# RollerBallRacerController.net
KiCad netlist of a schematic drawn in EAGLE
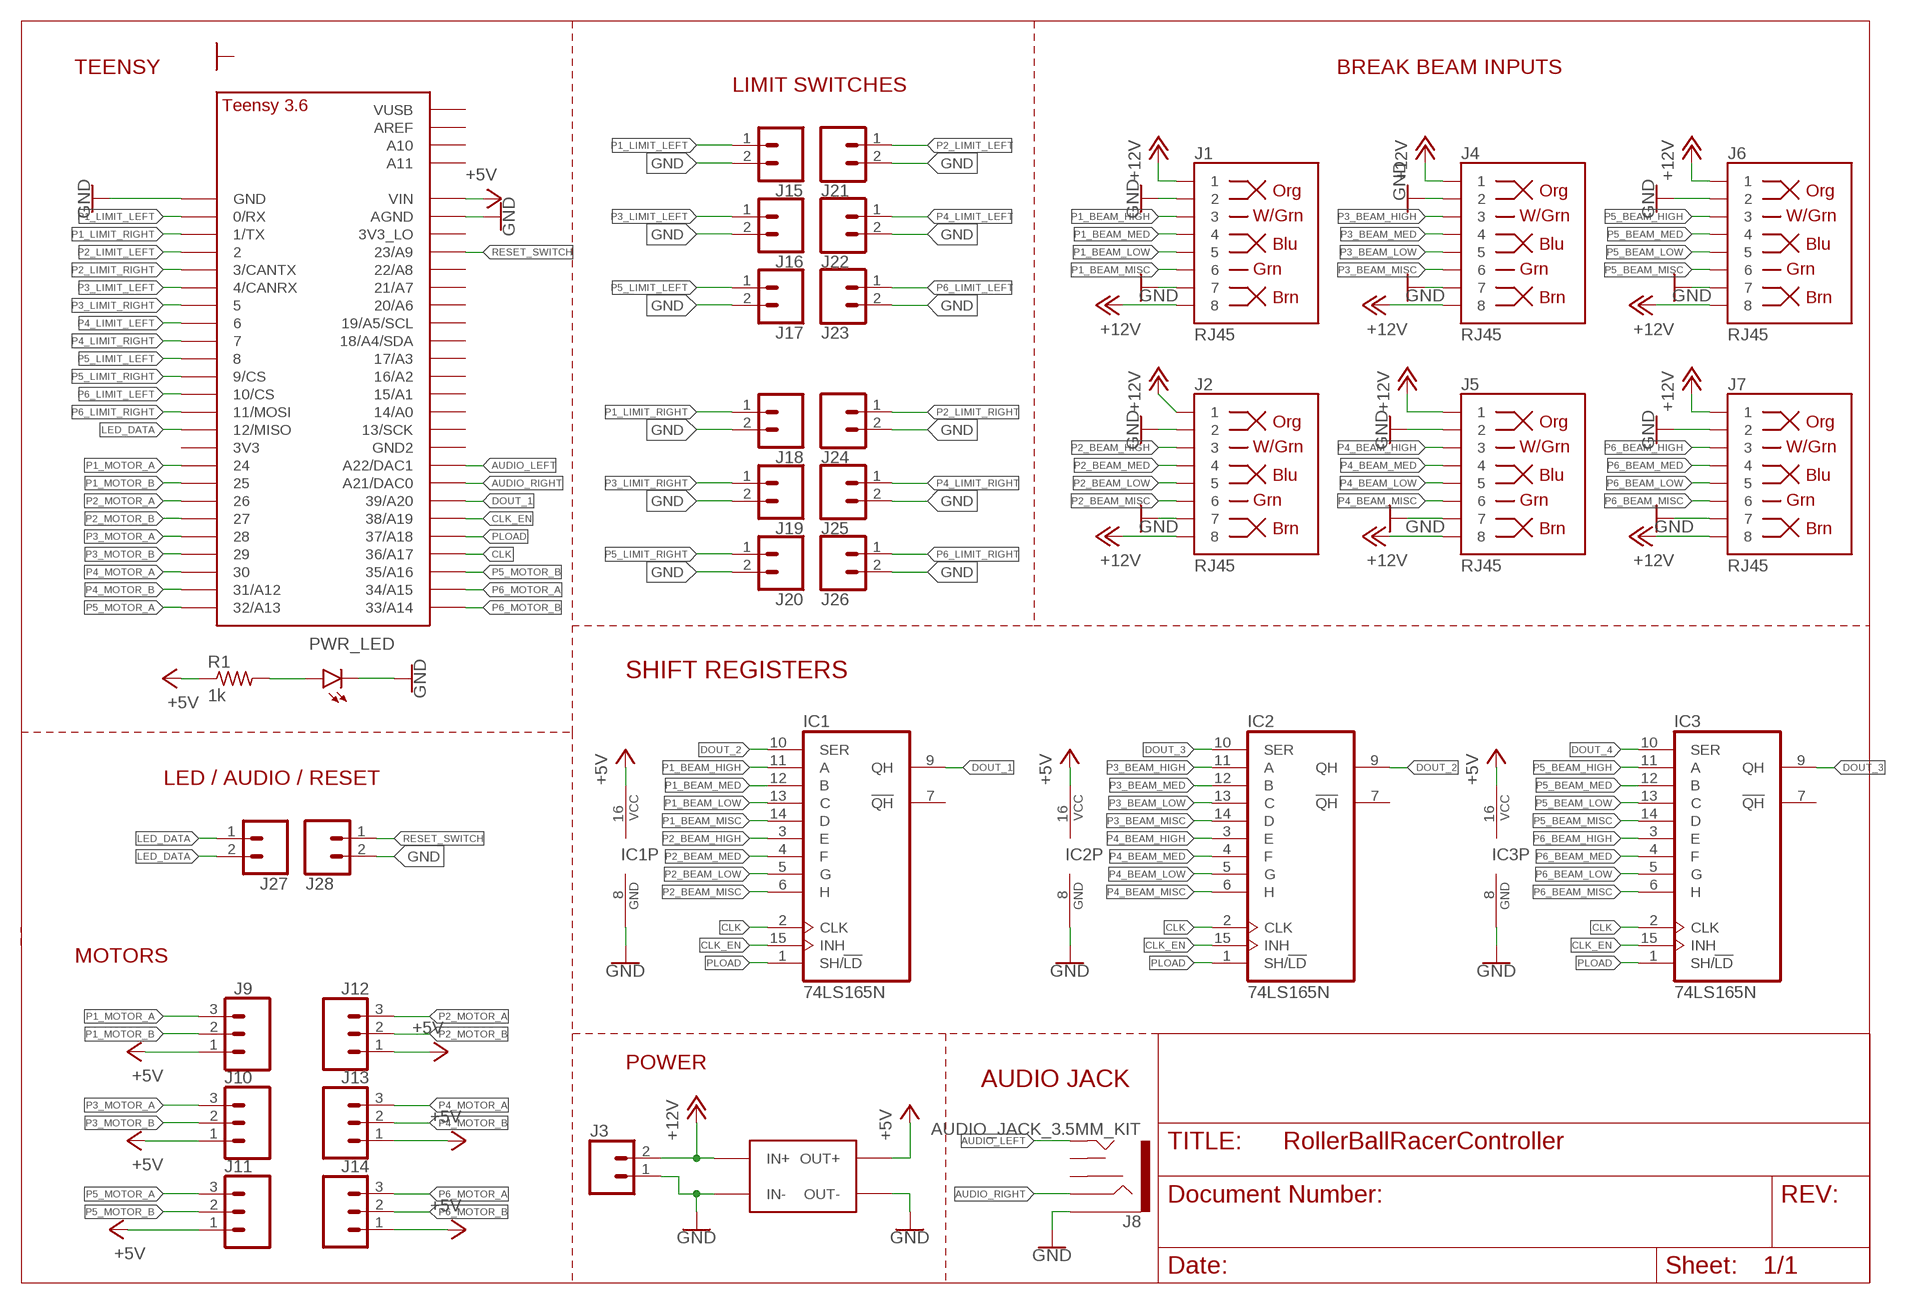
[diagram p0: schematic, sheet 1]

(export (version "E")
  (design (tool "Eeschema 10.0.6"))
  (components
    (comp (ref "IC1")
      (value "74LS165N")
      (footprint "eagle-import:DIL16")
      (libsource (lib "eagle-import") (part "74165NLS"))
    )
    (comp (ref "IC2")
      (value "74LS165N")
      (footprint "eagle-import:DIL16")
      (libsource (lib "eagle-import") (part "74165NLS"))
    )
    (comp (ref "IC3")
      (value "74LS165N")
      (footprint "eagle-import:DIL16")
      (libsource (lib "eagle-import") (part "74165NLS"))
    )
    (comp (ref "J1")
      (value "RJ45")
      (footprint "eagle-import:RJ45-8")
      (libsource (lib "eagle-import") (part "RJ45-8"))
    )
    (comp (ref "J2")
      (value "RJ45")
      (footprint "eagle-import:RJ45-8")
      (libsource (lib "eagle-import") (part "RJ45-8"))
    )
    (comp (ref "J3")
      (value "CONN_025MM")
      (footprint "eagle-import:SCREWTERMINAL-5MM-2")
      (libsource (lib "eagle-import") (part "CONN_025MM"))
    )
    (comp (ref "J4")
      (value "RJ45")
      (footprint "eagle-import:RJ45-8")
      (libsource (lib "eagle-import") (part "RJ45-8"))
    )
    (comp (ref "J5")
      (value "RJ45")
      (footprint "eagle-import:RJ45-8")
      (libsource (lib "eagle-import") (part "RJ45-8"))
    )
    (comp (ref "J6")
      (value "RJ45")
      (footprint "eagle-import:RJ45-8")
      (libsource (lib "eagle-import") (part "RJ45-8"))
    )
    (comp (ref "J7")
      (value "RJ45")
      (footprint "eagle-import:RJ45-8")
      (libsource (lib "eagle-import") (part "RJ45-8"))
    )
    (comp (ref "J8")
      (value "AUDIO_JACK_3.5MM_KIT")
      (footprint "eagle-import:AUDIO-JACK-KIT")
      (libsource (lib "eagle-import") (part "AUDIO_JACK_3.5MM_KIT"))
    )
    (comp (ref "J9")
      (value "CONN_03POLAR")
      (footprint "eagle-import:MOLEX-1X3")
      (libsource (lib "eagle-import") (part "CONN_03POLAR"))
    )
    (comp (ref "J10")
      (value "CONN_03POLAR")
      (footprint "eagle-import:MOLEX-1X3")
      (libsource (lib "eagle-import") (part "CONN_03POLAR"))
    )
    (comp (ref "J11")
      (value "CONN_03POLAR")
      (footprint "eagle-import:MOLEX-1X3")
      (libsource (lib "eagle-import") (part "CONN_03POLAR"))
    )
    (comp (ref "J12")
      (value "CONN_03POLAR")
      (footprint "eagle-import:MOLEX-1X3")
      (libsource (lib "eagle-import") (part "CONN_03POLAR"))
    )
    (comp (ref "J13")
      (value "CONN_03POLAR")
      (footprint "eagle-import:MOLEX-1X3")
      (libsource (lib "eagle-import") (part "CONN_03POLAR"))
    )
    (comp (ref "J14")
      (value "CONN_03POLAR")
      (footprint "eagle-import:MOLEX-1X3")
      (libsource (lib "eagle-import") (part "CONN_03POLAR"))
    )
    (comp (ref "J15")
      (value "CONN_02POLAR")
      (footprint "eagle-import:MOLEX-1X2")
      (libsource (lib "eagle-import") (part "CONN_02POLAR"))
    )
    (comp (ref "J16")
      (value "CONN_02POLAR")
      (footprint "eagle-import:MOLEX-1X2")
      (libsource (lib "eagle-import") (part "CONN_02POLAR"))
    )
    (comp (ref "J17")
      (value "CONN_02POLAR")
      (footprint "eagle-import:MOLEX-1X2")
      (libsource (lib "eagle-import") (part "CONN_02POLAR"))
    )
    (comp (ref "J18")
      (value "CONN_02POLAR")
      (footprint "eagle-import:MOLEX-1X2")
      (libsource (lib "eagle-import") (part "CONN_02POLAR"))
    )
    (comp (ref "J19")
      (value "CONN_02POLAR")
      (footprint "eagle-import:MOLEX-1X2")
      (libsource (lib "eagle-import") (part "CONN_02POLAR"))
    )
    (comp (ref "J20")
      (value "CONN_02POLAR")
      (footprint "eagle-import:MOLEX-1X2")
      (libsource (lib "eagle-import") (part "CONN_02POLAR"))
    )
    (comp (ref "J21")
      (value "CONN_02POLAR")
      (footprint "eagle-import:MOLEX-1X2")
      (libsource (lib "eagle-import") (part "CONN_02POLAR"))
    )
    (comp (ref "J22")
      (value "CONN_02POLAR")
      (footprint "eagle-import:MOLEX-1X2")
      (libsource (lib "eagle-import") (part "CONN_02POLAR"))
    )
    (comp (ref "J23")
      (value "CONN_02POLAR")
      (footprint "eagle-import:MOLEX-1X2")
      (libsource (lib "eagle-import") (part "CONN_02POLAR"))
    )
    (comp (ref "J24")
      (value "CONN_02POLAR")
      (footprint "eagle-import:MOLEX-1X2")
      (libsource (lib "eagle-import") (part "CONN_02POLAR"))
    )
    (comp (ref "J25")
      (value "CONN_02POLAR")
      (footprint "eagle-import:MOLEX-1X2")
      (libsource (lib "eagle-import") (part "CONN_02POLAR"))
    )
    (comp (ref "J26")
      (value "CONN_02POLAR")
      (footprint "eagle-import:MOLEX-1X2")
      (libsource (lib "eagle-import") (part "CONN_02POLAR"))
    )
    (comp (ref "J27")
      (value "CONN_02POLAR")
      (footprint "eagle-import:MOLEX-1X2")
      (libsource (lib "eagle-import") (part "CONN_02POLAR"))
    )
    (comp (ref "J28")
      (value "CONN_02POLAR")
      (footprint "eagle-import:MOLEX-1X2")
      (libsource (lib "eagle-import") (part "CONN_02POLAR"))
    )
    (comp (ref "PWR_LED")
      (value "LED5MM")
      (footprint "eagle-import:LED5MM")
      (libsource (lib "eagle-import") (part "LED5MM"))
    )
    (comp (ref "R1")
      (value "1k")
      (footprint "eagle-import:0204_7")
      (libsource (lib "eagle-import") (part "R-US_0204/7"))
    )
    (comp (ref "U$2")
      (value "LM2956_DC_DC")
      (footprint "eagle-import:LM2596")
      (libsource (lib "eagle-import") (part "LM2956_DC_DC"))
    )
    (comp (ref "U$3")
      (value "TEENSY_3.5/3.6_BASIC")
      (footprint "eagle-import:TEENSY_3.5_3.6_BASIC")
      (libsource (lib "eagle-import") (part "TEENSY_3.5/3.6_BASIC"))
    )
  )
  (nets
    (net (code "1") (name "+5V") (class "Default")
      (node (ref "IC1") (pin "16") (pinfunction "VCC_16") (pintype "power_in"))
      (node (ref "IC2") (pin "16") (pinfunction "VCC_16") (pintype "power_in"))
      (node (ref "IC3") (pin "16") (pinfunction "VCC_16") (pintype "power_in"))
      (node (ref "J10") (pin "1") (pinfunction "1_1") (pintype "passive"))
      (node (ref "J11") (pin "1") (pinfunction "1_1") (pintype "passive"))
      (node (ref "J12") (pin "1") (pinfunction "1_1") (pintype "passive"))
      (node (ref "J13") (pin "1") (pinfunction "1_1") (pintype "passive"))
      (node (ref "J14") (pin "1") (pinfunction "1_1") (pintype "passive"))
      (node (ref "J9") (pin "1") (pinfunction "1_1") (pintype "passive"))
      (node (ref "R1") (pin "1") (pinfunction "1_1") (pintype "passive"))
      (node (ref "U$2") (pin "P$4") (pinfunction "OUT+_P$4") (pintype "bidirectional"))
      (node (ref "U$3") (pin "VIN") (pinfunction "VIN_VIN") (pintype "bidirectional"))
    )
    (net (code "2") (name "+12V") (class "Default")
      (node (ref "J1") (pin "1") (pinfunction "1_1") (pintype "bidirectional"))
      (node (ref "J1") (pin "8") (pinfunction "8_8") (pintype "bidirectional"))
      (node (ref "J2") (pin "1") (pinfunction "1_1") (pintype "bidirectional"))
      (node (ref "J2") (pin "8") (pinfunction "8_8") (pintype "bidirectional"))
      (node (ref "J3") (pin "2") (pinfunction "2_2") (pintype "passive"))
      (node (ref "J4") (pin "1") (pinfunction "1_1") (pintype "bidirectional"))
      (node (ref "J4") (pin "8") (pinfunction "8_8") (pintype "bidirectional"))
      (node (ref "J5") (pin "1") (pinfunction "1_1") (pintype "bidirectional"))
      (node (ref "J5") (pin "8") (pinfunction "8_8") (pintype "bidirectional"))
      (node (ref "J6") (pin "1") (pinfunction "1_1") (pintype "bidirectional"))
      (node (ref "J6") (pin "8") (pinfunction "8_8") (pintype "bidirectional"))
      (node (ref "J7") (pin "1") (pinfunction "1_1") (pintype "bidirectional"))
      (node (ref "J7") (pin "8") (pinfunction "8_8") (pintype "bidirectional"))
      (node (ref "U$2") (pin "P$1") (pinfunction "IN+_P$1") (pintype "bidirectional"))
    )
    (net (code "3") (name "AUDIO_LEFT") (class "Default")
      (node (ref "J8") (pin "TIP") (pinfunction "TIP_TIP") (pintype "bidirectional"))
      (node (ref "U$3") (pin "A22/DAC1") (pinfunction "A22/DAC1_A22/DAC1") (pintype "bidirectional"))
    )
    (net (code "4") (name "AUDIO_RIGHT") (class "Default")
      (node (ref "J8") (pin "RING") (pinfunction "RING_RING") (pintype "bidirectional"))
      (node (ref "U$3") (pin "21/DAC0") (pinfunction "A21/DAC0_21/DAC0") (pintype "bidirectional"))
    )
    (net (code "5") (name "CLK") (class "Default")
      (node (ref "IC1") (pin "2") (pinfunction "CLK_2") (pintype "input"))
      (node (ref "IC2") (pin "2") (pinfunction "CLK_2") (pintype "input"))
      (node (ref "IC3") (pin "2") (pinfunction "CLK_2") (pintype "input"))
      (node (ref "U$3") (pin "36/A17") (pinfunction "36/A17_36/A17") (pintype "bidirectional"))
    )
    (net (code "6") (name "CLK_EN") (class "Default")
      (node (ref "IC1") (pin "15") (pinfunction "INH_15") (pintype "input"))
      (node (ref "IC2") (pin "15") (pinfunction "INH_15") (pintype "input"))
      (node (ref "IC3") (pin "15") (pinfunction "INH_15") (pintype "input"))
      (node (ref "U$3") (pin "38/A19") (pinfunction "38/A19_38/A19") (pintype "bidirectional"))
    )
    (net (code "7") (name "DOUT_1") (class "Default")
      (node (ref "IC1") (pin "9") (pinfunction "QH_9") (pintype "output"))
      (node (ref "U$3") (pin "39/A20") (pinfunction "39/A20_39/A20") (pintype "bidirectional"))
    )
    (net (code "8") (name "DOUT_2") (class "Default")
      (node (ref "IC1") (pin "10") (pinfunction "SER_10") (pintype "input"))
      (node (ref "IC2") (pin "9") (pinfunction "QH_9") (pintype "output"))
    )
    (net (code "9") (name "DOUT_3") (class "Default")
      (node (ref "IC2") (pin "10") (pinfunction "SER_10") (pintype "input"))
      (node (ref "IC3") (pin "9") (pinfunction "QH_9") (pintype "output"))
    )
    (net (code "10") (name "DOUT_4") (class "Default")
      (node (ref "IC3") (pin "10") (pinfunction "SER_10") (pintype "input"))
    )
    (net (code "11") (name "GND") (class "Default")
      (node (ref "IC1") (pin "8") (pinfunction "GND_8") (pintype "power_in"))
      (node (ref "IC2") (pin "8") (pinfunction "GND_8") (pintype "power_in"))
      (node (ref "IC3") (pin "8") (pinfunction "GND_8") (pintype "power_in"))
      (node (ref "J1") (pin "2") (pinfunction "2_2") (pintype "bidirectional"))
      (node (ref "J1") (pin "7") (pinfunction "7_7") (pintype "bidirectional"))
      (node (ref "J15") (pin "2") (pinfunction "2_2") (pintype "passive"))
      (node (ref "J16") (pin "2") (pinfunction "2_2") (pintype "passive"))
      (node (ref "J17") (pin "2") (pinfunction "2_2") (pintype "passive"))
      (node (ref "J18") (pin "2") (pinfunction "2_2") (pintype "passive"))
      (node (ref "J19") (pin "2") (pinfunction "2_2") (pintype "passive"))
      (node (ref "J2") (pin "2") (pinfunction "2_2") (pintype "bidirectional"))
      (node (ref "J2") (pin "7") (pinfunction "7_7") (pintype "bidirectional"))
      (node (ref "J20") (pin "2") (pinfunction "2_2") (pintype "passive"))
      (node (ref "J21") (pin "2") (pinfunction "2_2") (pintype "passive"))
      (node (ref "J22") (pin "2") (pinfunction "2_2") (pintype "passive"))
      (node (ref "J23") (pin "2") (pinfunction "2_2") (pintype "passive"))
      (node (ref "J24") (pin "2") (pinfunction "2_2") (pintype "passive"))
      (node (ref "J25") (pin "2") (pinfunction "2_2") (pintype "passive"))
      (node (ref "J26") (pin "2") (pinfunction "2_2") (pintype "passive"))
      (node (ref "J28") (pin "2") (pinfunction "2_2") (pintype "passive"))
      (node (ref "J3") (pin "1") (pinfunction "1_1") (pintype "passive"))
      (node (ref "J4") (pin "2") (pinfunction "2_2") (pintype "bidirectional"))
      (node (ref "J4") (pin "7") (pinfunction "7_7") (pintype "bidirectional"))
      (node (ref "J5") (pin "2") (pinfunction "2_2") (pintype "bidirectional"))
      (node (ref "J5") (pin "7") (pinfunction "7_7") (pintype "bidirectional"))
      (node (ref "J6") (pin "2") (pinfunction "2_2") (pintype "bidirectional"))
      (node (ref "J6") (pin "7") (pinfunction "7_7") (pintype "bidirectional"))
      (node (ref "J7") (pin "2") (pinfunction "2_2") (pintype "bidirectional"))
      (node (ref "J7") (pin "7") (pinfunction "7_7") (pintype "bidirectional"))
      (node (ref "J8") (pin "SLEEVE") (pinfunction "SLEEVE_SLEEVE") (pintype "bidirectional"))
      (node (ref "PWR_LED") (pin "K") (pinfunction "C_K") (pintype "passive"))
      (node (ref "U$2") (pin "P$2") (pinfunction "IN-_P$2") (pintype "bidirectional"))
      (node (ref "U$2") (pin "P$3") (pinfunction "OUT-_P$3") (pintype "bidirectional"))
      (node (ref "U$3") (pin "AGND") (pinfunction "AGND_AGND") (pintype "bidirectional"))
      (node (ref "U$3") (pin "GND") (pinfunction "GND_GND") (pintype "bidirectional"))
    )
    (net (code "12") (name "LED_DATA") (class "Default")
      (node (ref "J27") (pin "1") (pinfunction "1_1") (pintype "passive"))
      (node (ref "J27") (pin "2") (pinfunction "2_2") (pintype "passive"))
      (node (ref "U$3") (pin "12/MISO") (pinfunction "12/MISO_12/MISO") (pintype "bidirectional"))
    )
    (net (code "13") (name "Net-(PWR_LED-PadA)") (class "Default")
      (node (ref "PWR_LED") (pin "A") (pinfunction "A_A") (pintype "passive"))
      (node (ref "R1") (pin "2") (pinfunction "2_2") (pintype "passive"))
    )
    (net (code "14") (name "P1_BEAM_HIGH") (class "Default")
      (node (ref "IC1") (pin "11") (pinfunction "A_11") (pintype "input"))
      (node (ref "J1") (pin "3") (pinfunction "3_3") (pintype "bidirectional"))
    )
    (net (code "15") (name "P1_BEAM_LOW") (class "Default")
      (node (ref "IC1") (pin "13") (pinfunction "C_13") (pintype "input"))
      (node (ref "J1") (pin "5") (pinfunction "5_5") (pintype "bidirectional"))
    )
    (net (code "16") (name "P1_BEAM_MED") (class "Default")
      (node (ref "IC1") (pin "12") (pinfunction "B_12") (pintype "input"))
      (node (ref "J1") (pin "4") (pinfunction "4_4") (pintype "bidirectional"))
    )
    (net (code "17") (name "P1_BEAM_MISC") (class "Default")
      (node (ref "IC1") (pin "14") (pinfunction "D_14") (pintype "input"))
      (node (ref "J1") (pin "6") (pinfunction "6_6") (pintype "bidirectional"))
    )
    (net (code "18") (name "P1_LIMIT_LEFT") (class "Default")
      (node (ref "J15") (pin "1") (pinfunction "1_1") (pintype "passive"))
      (node (ref "U$3") (pin "0/RX") (pinfunction "0/RX_0/RX") (pintype "bidirectional"))
    )
    (net (code "19") (name "P1_LIMIT_RIGHT") (class "Default")
      (node (ref "J18") (pin "1") (pinfunction "1_1") (pintype "passive"))
      (node (ref "U$3") (pin "1/TX") (pinfunction "1/TX_1/TX") (pintype "bidirectional"))
    )
    (net (code "20") (name "P1_MOTOR_A") (class "Default")
      (node (ref "J9") (pin "3") (pinfunction "3_3") (pintype "passive"))
      (node (ref "U$3") (pin "24") (pinfunction "24_24") (pintype "bidirectional"))
    )
    (net (code "21") (name "P1_MOTOR_B") (class "Default")
      (node (ref "J9") (pin "2") (pinfunction "2_2") (pintype "passive"))
      (node (ref "U$3") (pin "25") (pinfunction "25_25") (pintype "bidirectional"))
    )
    (net (code "22") (name "P2_BEAM_HIGH") (class "Default")
      (node (ref "IC1") (pin "3") (pinfunction "E_3") (pintype "input"))
      (node (ref "J2") (pin "3") (pinfunction "3_3") (pintype "bidirectional"))
    )
    (net (code "23") (name "P2_BEAM_LOW") (class "Default")
      (node (ref "IC1") (pin "5") (pinfunction "G_5") (pintype "input"))
      (node (ref "J2") (pin "5") (pinfunction "5_5") (pintype "bidirectional"))
    )
    (net (code "24") (name "P2_BEAM_MED") (class "Default")
      (node (ref "IC1") (pin "4") (pinfunction "F_4") (pintype "input"))
      (node (ref "J2") (pin "4") (pinfunction "4_4") (pintype "bidirectional"))
    )
    (net (code "25") (name "P2_BEAM_MISC") (class "Default")
      (node (ref "IC1") (pin "6") (pinfunction "H_6") (pintype "input"))
      (node (ref "J2") (pin "6") (pinfunction "6_6") (pintype "bidirectional"))
    )
    (net (code "26") (name "P2_LIMIT_LEFT") (class "Default")
      (node (ref "J21") (pin "1") (pinfunction "1_1") (pintype "passive"))
      (node (ref "U$3") (pin "2") (pinfunction "2_2") (pintype "bidirectional"))
    )
    (net (code "27") (name "P2_LIMIT_RIGHT") (class "Default")
      (node (ref "J24") (pin "1") (pinfunction "1_1") (pintype "passive"))
      (node (ref "U$3") (pin "3/CANTX") (pinfunction "3/CANTX_3/CANTX") (pintype "bidirectional"))
    )
    (net (code "28") (name "P2_MOTOR_A") (class "Default")
      (node (ref "J12") (pin "3") (pinfunction "3_3") (pintype "passive"))
      (node (ref "U$3") (pin "26") (pinfunction "26_26") (pintype "bidirectional"))
    )
    (net (code "29") (name "P2_MOTOR_B") (class "Default")
      (node (ref "J12") (pin "2") (pinfunction "2_2") (pintype "passive"))
      (node (ref "U$3") (pin "27") (pinfunction "27_27") (pintype "bidirectional"))
    )
    (net (code "30") (name "P3_BEAM_HIGH") (class "Default")
      (node (ref "IC2") (pin "11") (pinfunction "A_11") (pintype "input"))
      (node (ref "J4") (pin "3") (pinfunction "3_3") (pintype "bidirectional"))
    )
    (net (code "31") (name "P3_BEAM_LOW") (class "Default")
      (node (ref "IC2") (pin "13") (pinfunction "C_13") (pintype "input"))
      (node (ref "J4") (pin "5") (pinfunction "5_5") (pintype "bidirectional"))
    )
    (net (code "32") (name "P3_BEAM_MED") (class "Default")
      (node (ref "IC2") (pin "12") (pinfunction "B_12") (pintype "input"))
      (node (ref "J4") (pin "4") (pinfunction "4_4") (pintype "bidirectional"))
    )
    (net (code "33") (name "P3_BEAM_MISC") (class "Default")
      (node (ref "IC2") (pin "14") (pinfunction "D_14") (pintype "input"))
      (node (ref "J4") (pin "6") (pinfunction "6_6") (pintype "bidirectional"))
    )
    (net (code "34") (name "P3_LIMIT_LEFT") (class "Default")
      (node (ref "J16") (pin "1") (pinfunction "1_1") (pintype "passive"))
      (node (ref "U$3") (pin "4/CANRX") (pinfunction "4/CANRX_4/CANRX") (pintype "bidirectional"))
    )
    (net (code "35") (name "P3_LIMIT_RIGHT") (class "Default")
      (node (ref "J19") (pin "1") (pinfunction "1_1") (pintype "passive"))
      (node (ref "U$3") (pin "5") (pinfunction "5_5") (pintype "bidirectional"))
    )
    (net (code "36") (name "P3_MOTOR_A") (class "Default")
      (node (ref "J10") (pin "3") (pinfunction "3_3") (pintype "passive"))
      (node (ref "U$3") (pin "28") (pinfunction "28_28") (pintype "bidirectional"))
    )
    (net (code "37") (name "P3_MOTOR_B") (class "Default")
      (node (ref "J10") (pin "2") (pinfunction "2_2") (pintype "passive"))
      (node (ref "U$3") (pin "29") (pinfunction "29_29") (pintype "bidirectional"))
    )
    (net (code "38") (name "P4_BEAM_HIGH") (class "Default")
      (node (ref "IC2") (pin "3") (pinfunction "E_3") (pintype "input"))
      (node (ref "J5") (pin "3") (pinfunction "3_3") (pintype "bidirectional"))
    )
    (net (code "39") (name "P4_BEAM_LOW") (class "Default")
      (node (ref "IC2") (pin "5") (pinfunction "G_5") (pintype "input"))
      (node (ref "J5") (pin "5") (pinfunction "5_5") (pintype "bidirectional"))
    )
    (net (code "40") (name "P4_BEAM_MED") (class "Default")
      (node (ref "IC2") (pin "4") (pinfunction "F_4") (pintype "input"))
      (node (ref "J5") (pin "4") (pinfunction "4_4") (pintype "bidirectional"))
    )
    (net (code "41") (name "P4_BEAM_MISC") (class "Default")
      (node (ref "IC2") (pin "6") (pinfunction "H_6") (pintype "input"))
      (node (ref "J5") (pin "6") (pinfunction "6_6") (pintype "bidirectional"))
    )
    (net (code "42") (name "P4_LIMIT_LEFT") (class "Default")
      (node (ref "J22") (pin "1") (pinfunction "1_1") (pintype "passive"))
      (node (ref "U$3") (pin "6") (pinfunction "6_6") (pintype "bidirectional"))
    )
    (net (code "43") (name "P4_LIMIT_RIGHT") (class "Default")
      (node (ref "J25") (pin "1") (pinfunction "1_1") (pintype "passive"))
      (node (ref "U$3") (pin "7") (pinfunction "7_7") (pintype "bidirectional"))
    )
    (net (code "44") (name "P4_MOTOR_A") (class "Default")
      (node (ref "J13") (pin "3") (pinfunction "3_3") (pintype "passive"))
      (node (ref "U$3") (pin "30") (pinfunction "30_30") (pintype "bidirectional"))
    )
    (net (code "45") (name "P4_MOTOR_B") (class "Default")
      (node (ref "J13") (pin "2") (pinfunction "2_2") (pintype "passive"))
      (node (ref "U$3") (pin "31/A12") (pinfunction "31/A12_31/A12") (pintype "bidirectional"))
    )
    (net (code "46") (name "P5_BEAM_HIGH") (class "Default")
      (node (ref "IC3") (pin "11") (pinfunction "A_11") (pintype "input"))
      (node (ref "J6") (pin "3") (pinfunction "3_3") (pintype "bidirectional"))
    )
    (net (code "47") (name "P5_BEAM_LOW") (class "Default")
      (node (ref "IC3") (pin "13") (pinfunction "C_13") (pintype "input"))
      (node (ref "J6") (pin "5") (pinfunction "5_5") (pintype "bidirectional"))
    )
    (net (code "48") (name "P5_BEAM_MED") (class "Default")
      (node (ref "IC3") (pin "12") (pinfunction "B_12") (pintype "input"))
      (node (ref "J6") (pin "4") (pinfunction "4_4") (pintype "bidirectional"))
    )
    (net (code "49") (name "P5_BEAM_MISC") (class "Default")
      (node (ref "IC3") (pin "14") (pinfunction "D_14") (pintype "input"))
      (node (ref "J6") (pin "6") (pinfunction "6_6") (pintype "bidirectional"))
    )
    (net (code "50") (name "P5_LIMIT_LEFT") (class "Default")
      (node (ref "J17") (pin "1") (pinfunction "1_1") (pintype "passive"))
      (node (ref "U$3") (pin "8") (pinfunction "8_8") (pintype "bidirectional"))
    )
    (net (code "51") (name "P5_LIMIT_RIGHT") (class "Default")
      (node (ref "J20") (pin "1") (pinfunction "1_1") (pintype "passive"))
      (node (ref "U$3") (pin "9/CS") (pinfunction "9/CS_9/CS") (pintype "bidirectional"))
    )
    (net (code "52") (name "P5_MOTOR_A") (class "Default")
      (node (ref "J11") (pin "3") (pinfunction "3_3") (pintype "passive"))
      (node (ref "U$3") (pin "32/A13") (pinfunction "32/A13_32/A13") (pintype "bidirectional"))
    )
    (net (code "53") (name "P5_MOTOR_B") (class "Default")
      (node (ref "J11") (pin "2") (pinfunction "2_2") (pintype "passive"))
      (node (ref "U$3") (pin "35/A16") (pinfunction "35/A16_35/A16") (pintype "bidirectional"))
    )
    (net (code "54") (name "P6_BEAM_HIGH") (class "Default")
      (node (ref "IC3") (pin "3") (pinfunction "E_3") (pintype "input"))
      (node (ref "J7") (pin "3") (pinfunction "3_3") (pintype "bidirectional"))
    )
    (net (code "55") (name "P6_BEAM_LOW") (class "Default")
      (node (ref "IC3") (pin "5") (pinfunction "G_5") (pintype "input"))
      (node (ref "J7") (pin "5") (pinfunction "5_5") (pintype "bidirectional"))
    )
    (net (code "56") (name "P6_BEAM_MED") (class "Default")
      (node (ref "IC3") (pin "4") (pinfunction "F_4") (pintype "input"))
      (node (ref "J7") (pin "4") (pinfunction "4_4") (pintype "bidirectional"))
    )
    (net (code "57") (name "P6_BEAM_MISC") (class "Default")
      (node (ref "IC3") (pin "6") (pinfunction "H_6") (pintype "input"))
      (node (ref "J7") (pin "6") (pinfunction "6_6") (pintype "bidirectional"))
    )
    (net (code "58") (name "P6_LIMIT_LEFT") (class "Default")
      (node (ref "J23") (pin "1") (pinfunction "1_1") (pintype "passive"))
      (node (ref "U$3") (pin "10/CS") (pinfunction "10/CS_10/CS") (pintype "bidirectional"))
    )
    (net (code "59") (name "P6_LIMIT_RIGHT") (class "Default")
      (node (ref "J26") (pin "1") (pinfunction "1_1") (pintype "passive"))
      (node (ref "U$3") (pin "11/MOSI") (pinfunction "11/MOSI_11/MOSI") (pintype "bidirectional"))
    )
    (net (code "60") (name "P6_MOTOR_A") (class "Default")
      (node (ref "J14") (pin "3") (pinfunction "3_3") (pintype "passive"))
      (node (ref "U$3") (pin "34/A15") (pinfunction "34/A15_34/A15") (pintype "bidirectional"))
    )
    (net (code "61") (name "P6_MOTOR_B") (class "Default")
      (node (ref "J14") (pin "2") (pinfunction "2_2") (pintype "passive"))
      (node (ref "U$3") (pin "33/A14") (pinfunction "33/A14_33/A14") (pintype "bidirectional"))
    )
    (net (code "62") (name "PLOAD") (class "Default")
      (node (ref "IC1") (pin "1") (pinfunction "SH/~{LD}_1") (pintype "input"))
      (node (ref "IC2") (pin "1") (pinfunction "SH/~{LD}_1") (pintype "input"))
      (node (ref "IC3") (pin "1") (pinfunction "SH/~{LD}_1") (pintype "input"))
      (node (ref "U$3") (pin "37/A18") (pinfunction "37/A18_37/A18") (pintype "bidirectional"))
    )
    (net (code "63") (name "RESET_SWITCH") (class "Default")
      (node (ref "J28") (pin "1") (pinfunction "1_1") (pintype "passive"))
      (node (ref "U$3") (pin "23/A9") (pinfunction "23/A9_23/A9") (pintype "bidirectional"))
    )
    (net (code "64") (name "unconnected-(IC1A-~{QH}-Pad7)") (class "Default")
      (node (ref "IC1") (pin "7") (pinfunction "~{QH}_7") (pintype "output"))
    )
    (net (code "65") (name "unconnected-(IC2A-~{QH}-Pad7)") (class "Default")
      (node (ref "IC2") (pin "7") (pinfunction "~{QH}_7") (pintype "output"))
    )
    (net (code "66") (name "unconnected-(IC3A-~{QH}-Pad7)") (class "Default")
      (node (ref "IC3") (pin "7") (pinfunction "~{QH}_7") (pintype "output"))
    )
    (net (code "67") (name "unconnected-(J8-PadRSH)") (class "Default")
      (node (ref "J8") (pin "RSH") (pinfunction "RSH_RSH") (pintype "bidirectional"))
    )
    (net (code "68") (name "unconnected-(J8-PadTSH)") (class "Default")
      (node (ref "J8") (pin "TSH") (pinfunction "TSH_TSH") (pintype "bidirectional"))
    )
    (net (code "69") (name "unconnected-(U$3-Pad3V3)") (class "Default")
      (node (ref "U$3") (pin "3V3") (pinfunction "3V3_3V3") (pintype "bidirectional"))
    )
    (net (code "70") (name "unconnected-(U$3-Pad3V3_LO)") (class "Default")
      (node (ref "U$3") (pin "3V3_LO") (pinfunction "3V3_LO_3V3_LO") (pintype "bidirectional"))
    )
    (net (code "71") (name "unconnected-(U$3-Pad13{slash}SCK)") (class "Default")
      (node (ref "U$3") (pin "13/SCK") (pinfunction "13/SCK_13/SCK") (pintype "bidirectional"))
    )
    (net (code "72") (name "unconnected-(U$3-Pad14{slash}A0)") (class "Default")
      (node (ref "U$3") (pin "14/A0") (pinfunction "14/A0_14/A0") (pintype "bidirectional"))
    )
    (net (code "73") (name "unconnected-(U$3-Pad15{slash}A1)") (class "Default")
      (node (ref "U$3") (pin "15/A1") (pinfunction "15/A1_15/A1") (pintype "bidirectional"))
    )
    (net (code "74") (name "unconnected-(U$3-Pad16{slash}A2)") (class "Default")
      (node (ref "U$3") (pin "16/A2") (pinfunction "16/A2_16/A2") (pintype "bidirectional"))
    )
    (net (code "75") (name "unconnected-(U$3-Pad17{slash}A3)") (class "Default")
      (node (ref "U$3") (pin "17/A3") (pinfunction "17/A3_17/A3") (pintype "bidirectional"))
    )
    (net (code "76") (name "unconnected-(U$3-Pad18{slash}A4{slash}SDA)") (class "Default")
      (node (ref "U$3") (pin "18/A4/SDA") (pinfunction "18/A4/SDA_18/A4/SDA") (pintype "bidirectional"))
    )
    (net (code "77") (name "unconnected-(U$3-Pad19{slash}A5{slash}SCL)") (class "Default")
      (node (ref "U$3") (pin "19/A5/SCL") (pinfunction "19/A5/SCL_19/A5/SCL") (pintype "bidirectional"))
    )
    (net (code "78") (name "unconnected-(U$3-Pad20{slash}A6)") (class "Default")
      (node (ref "U$3") (pin "20/A6") (pinfunction "20/A6_20/A6") (pintype "bidirectional"))
    )
    (net (code "79") (name "unconnected-(U$3-Pad21{slash}A7)") (class "Default")
      (node (ref "U$3") (pin "21/A7") (pinfunction "21/A7_21/A7") (pintype "bidirectional"))
    )
    (net (code "80") (name "unconnected-(U$3-Pad22{slash}A8)") (class "Default")
      (node (ref "U$3") (pin "22/A8") (pinfunction "22/A8_22/A8") (pintype "bidirectional"))
    )
    (net (code "81") (name "unconnected-(U$3-PadA10)") (class "Default")
      (node (ref "U$3") (pin "A10") (pinfunction "A10_A10") (pintype "bidirectional"))
    )
    (net (code "82") (name "unconnected-(U$3-PadA11)") (class "Default")
      (node (ref "U$3") (pin "A11") (pinfunction "A11_A11") (pintype "bidirectional"))
    )
    (net (code "83") (name "unconnected-(U$3-PadAREF)") (class "Default")
      (node (ref "U$3") (pin "AREF") (pinfunction "AREF_AREF") (pintype "bidirectional"))
    )
    (net (code "84") (name "unconnected-(U$3-PadGND2)") (class "Default")
      (node (ref "U$3") (pin "GND2") (pinfunction "GND2_GND2") (pintype "bidirectional"))
    )
    (net (code "85") (name "unconnected-(U$3-PadVUSB)") (class "Default")
      (node (ref "U$3") (pin "VUSB") (pinfunction "VUSB_VUSB") (pintype "bidirectional"))
    )
  )
)
